# main.net
KiCad netlist of a schematic drawn in EAGLE
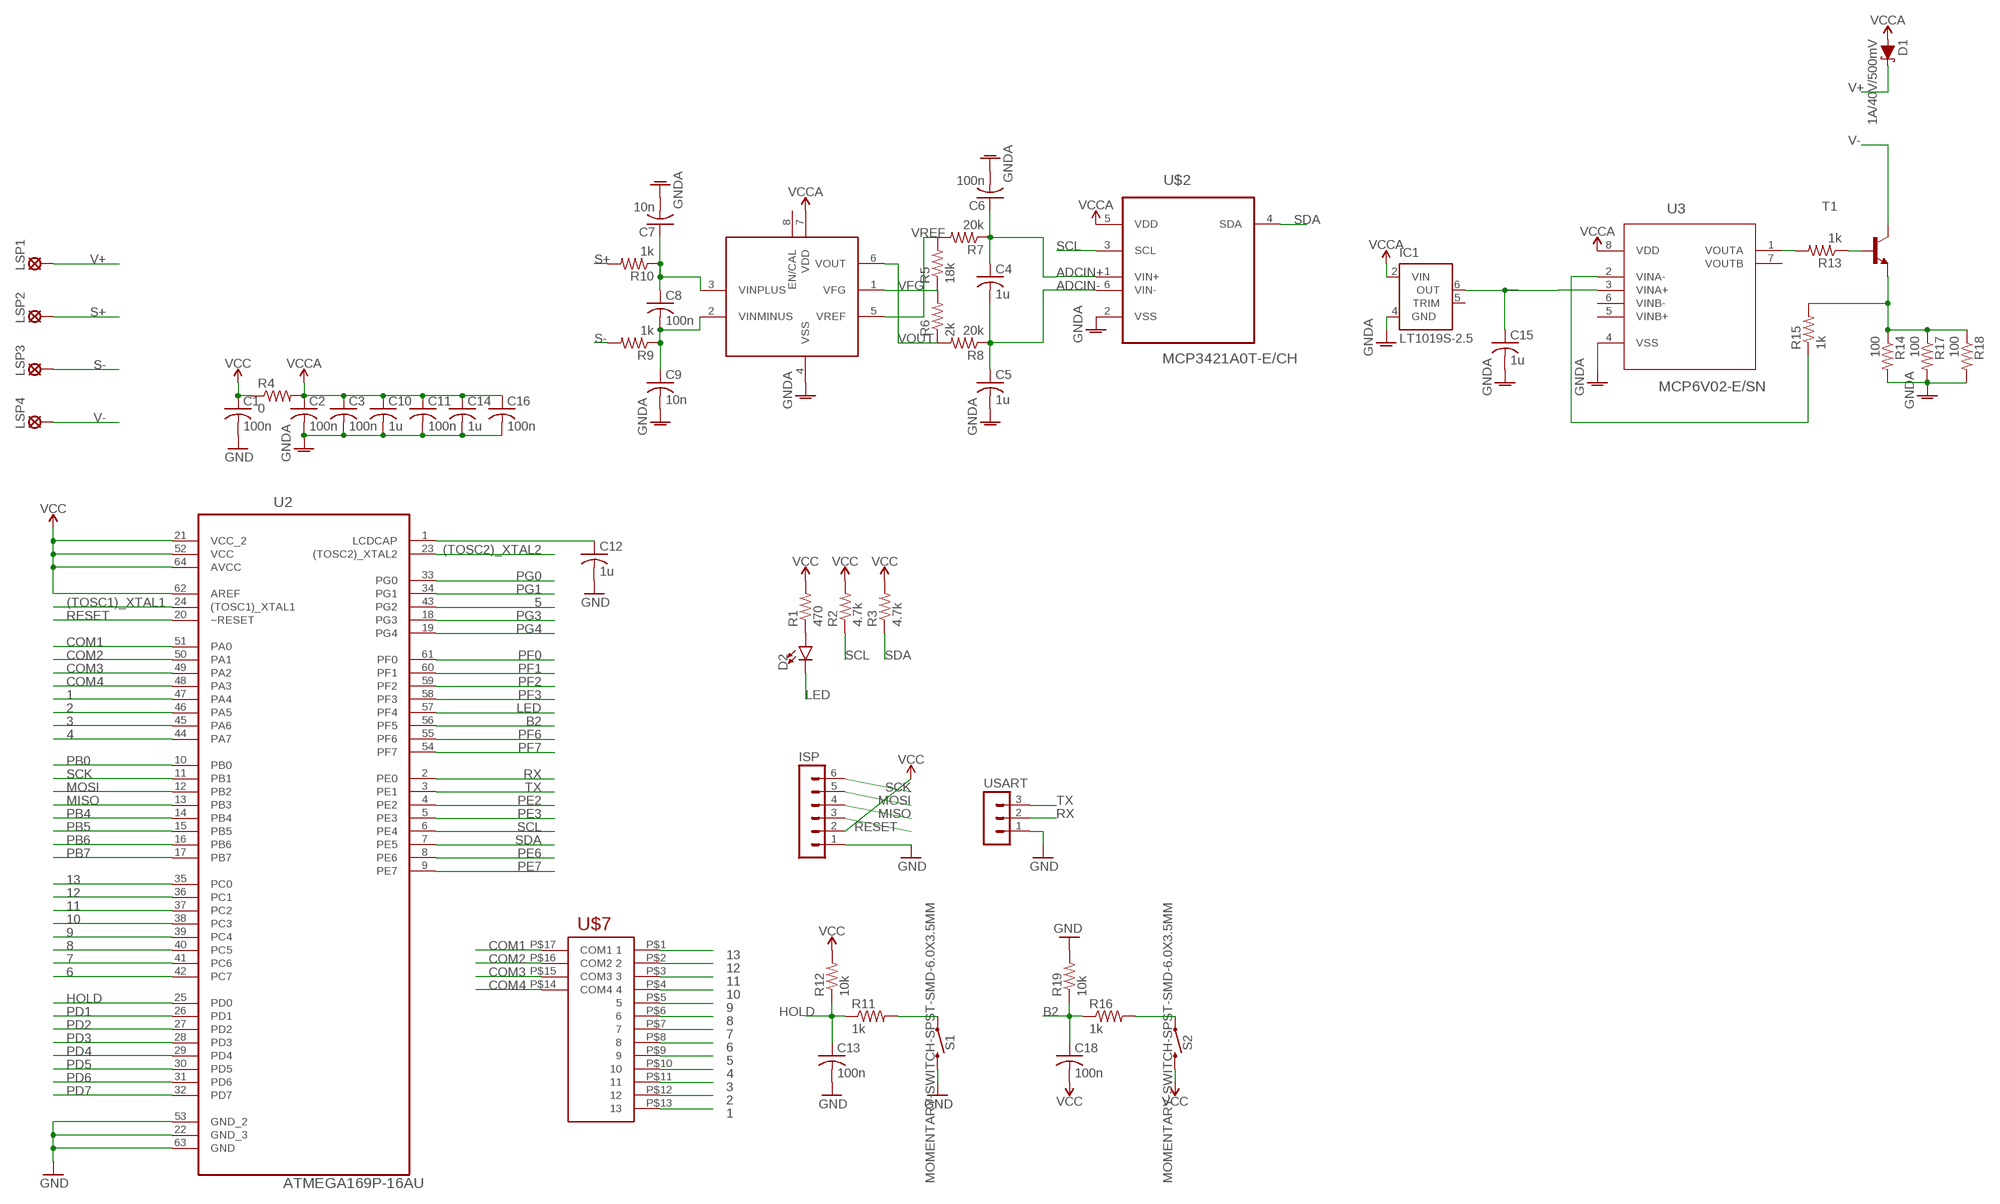
[diagram p0: schematic, sheet 1]

(export (version "E")
  (design (tool "Eeschema 10.0.6"))
  (components
    (comp (ref "C1")
      (value "100n")
      (footprint "eagle-import:C0603")
      (libsource (lib "eagle-import") (part "C-USC0603"))
    )
    (comp (ref "C2")
      (value "100n")
      (footprint "eagle-import:C0603")
      (libsource (lib "eagle-import") (part "C-USC0603"))
    )
    (comp (ref "C3")
      (value "100n")
      (footprint "eagle-import:C0603")
      (libsource (lib "eagle-import") (part "C-USC0603"))
    )
    (comp (ref "C4")
      (value "1u")
      (footprint "eagle-import:C0603")
      (libsource (lib "eagle-import") (part "C-USC0603"))
    )
    (comp (ref "C5")
      (value "1u")
      (footprint "eagle-import:C0603")
      (libsource (lib "eagle-import") (part "C-USC0603"))
    )
    (comp (ref "C6")
      (value "100n")
      (footprint "eagle-import:C0603")
      (libsource (lib "eagle-import") (part "C-USC0603"))
    )
    (comp (ref "C7")
      (value "10n")
      (footprint "eagle-import:C0603")
      (libsource (lib "eagle-import") (part "C-USC0603"))
    )
    (comp (ref "C8")
      (value "100n")
      (footprint "eagle-import:C0603")
      (libsource (lib "eagle-import") (part "C-USC0603"))
    )
    (comp (ref "C9")
      (value "10n")
      (footprint "eagle-import:C0603")
      (libsource (lib "eagle-import") (part "C-USC0603"))
    )
    (comp (ref "C10")
      (value "1u")
      (footprint "eagle-import:C0603")
      (libsource (lib "eagle-import") (part "C-USC0603"))
    )
    (comp (ref "C11")
      (value "100n")
      (footprint "eagle-import:C0603")
      (libsource (lib "eagle-import") (part "C-USC0603"))
    )
    (comp (ref "C12")
      (value "1u")
      (footprint "eagle-import:C0603")
      (libsource (lib "eagle-import") (part "C-USC0603"))
    )
    (comp (ref "C13")
      (value "100n")
      (footprint "eagle-import:C0603")
      (libsource (lib "eagle-import") (part "C-USC0603"))
    )
    (comp (ref "C14")
      (value "1u")
      (footprint "eagle-import:C0603")
      (libsource (lib "eagle-import") (part "C-USC0603"))
    )
    (comp (ref "C15")
      (value "1u")
      (footprint "eagle-import:C0603")
      (libsource (lib "eagle-import") (part "C-USC0603"))
    )
    (comp (ref "C16")
      (value "100n")
      (footprint "eagle-import:C0603")
      (libsource (lib "eagle-import") (part "C-USC0603"))
    )
    (comp (ref "C18")
      (value "100n")
      (footprint "eagle-import:C0603")
      (libsource (lib "eagle-import") (part "C-USC0603"))
    )
    (comp (ref "D1")
      (value "1A/40V/500mV")
      (footprint "eagle-import:SMA-DIODE")
      (libsource (lib "eagle-import") (part "DIODE-SCHOTTKY-SS14"))
    )
    (comp (ref "D2")
      (value "LED5MM")
      (footprint "eagle-import:LED_5MM")
      (libsource (lib "eagle-import") (part "LED5MM"))
    )
    (comp (ref "IC1")
      (value "LT1019S-2.5")
      (footprint "eagle-import:SOIC8")
      (fields (field (name "MPN") "LT1019CS8-2.5#PBF"))
      (libsource (lib "eagle-import") (part "LT1019?S-2.5"))
    )
    (comp (ref "ISP")
      (value "MA06-1")
      (footprint "eagle-import:MA06-1")
      (libsource (lib "eagle-import") (part "MA06-1"))
    )
    (comp (ref "LSP1")
      (value "MCS08")
      (footprint "eagle-import:MCS08")
      (libsource (lib "eagle-import") (part "MCS08"))
    )
    (comp (ref "LSP2")
      (value "MCS08")
      (footprint "eagle-import:MCS08")
      (libsource (lib "eagle-import") (part "MCS08"))
    )
    (comp (ref "LSP3")
      (value "MCS08")
      (footprint "eagle-import:MCS08")
      (libsource (lib "eagle-import") (part "MCS08"))
    )
    (comp (ref "LSP4")
      (value "MCS08")
      (footprint "eagle-import:MCS08")
      (libsource (lib "eagle-import") (part "MCS08"))
    )
    (comp (ref "R1")
      (value "470")
      (footprint "eagle-import:R0603")
      (libsource (lib "eagle-import") (part "R-US_R0603"))
    )
    (comp (ref "R2")
      (value "4.7k")
      (footprint "eagle-import:R0603")
      (libsource (lib "eagle-import") (part "R-US_R0603"))
    )
    (comp (ref "R3")
      (value "4.7k")
      (footprint "eagle-import:R0603")
      (libsource (lib "eagle-import") (part "R-US_R0603"))
    )
    (comp (ref "R4")
      (value "0")
      (footprint "eagle-import:0309_12")
      (libsource (lib "eagle-import") (part "R-US_0309/12"))
    )
    (comp (ref "R5")
      (value "18k")
      (footprint "eagle-import:R0603")
      (libsource (lib "eagle-import") (part "R-US_R0603"))
    )
    (comp (ref "R6")
      (value "2k")
      (footprint "eagle-import:R0603")
      (libsource (lib "eagle-import") (part "R-US_R0603"))
    )
    (comp (ref "R7")
      (value "20k")
      (footprint "eagle-import:R0603")
      (libsource (lib "eagle-import") (part "R-US_R0603"))
    )
    (comp (ref "R8")
      (value "20k")
      (footprint "eagle-import:R0603")
      (libsource (lib "eagle-import") (part "R-US_R0603"))
    )
    (comp (ref "R9")
      (value "1k")
      (footprint "eagle-import:R0603")
      (libsource (lib "eagle-import") (part "R-US_R0603"))
    )
    (comp (ref "R10")
      (value "1k")
      (footprint "eagle-import:R0603")
      (libsource (lib "eagle-import") (part "R-US_R0603"))
    )
    (comp (ref "R11")
      (value "1k")
      (footprint "eagle-import:R0603")
      (libsource (lib "eagle-import") (part "R-US_R0603"))
    )
    (comp (ref "R12")
      (value "10k")
      (footprint "eagle-import:R0603")
      (libsource (lib "eagle-import") (part "R-US_R0603"))
    )
    (comp (ref "R13")
      (value "1k")
      (footprint "eagle-import:R0603")
      (libsource (lib "eagle-import") (part "R-US_R0603"))
    )
    (comp (ref "R14")
      (value "100")
      (footprint "eagle-import:R0603")
      (libsource (lib "eagle-import") (part "R-US_R0603"))
    )
    (comp (ref "R15")
      (value "1k")
      (footprint "eagle-import:R0603")
      (libsource (lib "eagle-import") (part "R-US_R0603"))
    )
    (comp (ref "R16")
      (value "1k")
      (footprint "eagle-import:R0603")
      (libsource (lib "eagle-import") (part "R-US_R0603"))
    )
    (comp (ref "R17")
      (value "100")
      (footprint "eagle-import:R0603")
      (libsource (lib "eagle-import") (part "R-US_R0603"))
    )
    (comp (ref "R18")
      (value "100")
      (footprint "eagle-import:R0603")
      (libsource (lib "eagle-import") (part "R-US_R0603"))
    )
    (comp (ref "R19")
      (value "10k")
      (footprint "eagle-import:R0603")
      (libsource (lib "eagle-import") (part "R-US_R0603"))
    )
    (comp (ref "S1")
      (value "MOMENTARY-SWITCH-SPST-SMD-6.0X3.5MM")
      (footprint "eagle-import:TACTILE_SWITCH_SMD_6.0X3.5MM")
      (libsource (lib "eagle-import") (part "MOMENTARY-SWITCH-SPST-SMD-6.0X3.5MM"))
    )
    (comp (ref "S2")
      (value "MOMENTARY-SWITCH-SPST-SMD-6.0X3.5MM")
      (footprint "eagle-import:TACTILE_SWITCH_SMD_6.0X3.5MM")
      (libsource (lib "eagle-import") (part "MOMENTARY-SWITCH-SPST-SMD-6.0X3.5MM"))
    )
    (comp (ref "T1")
      (value "MMBT3904LT1-NPN-SOT23-BEC")
      (footprint "eagle-import:SOT23-BEC")
      (libsource (lib "eagle-import") (part "-NPN-SOT23-BECMMBT3904LT1"))
    )
    (comp (ref "U$2")
      (value "MCP3421A0T-E/CH")
      (footprint "eagle-import:SOT95P270X145-6N")
      (libsource (lib "eagle-import") (part "MCP3421A0T-E/CH"))
    )
    (comp (ref "U$3")
      (value "MCP6N11")
      (footprint "eagle-import:SOIC8")
      (libsource (lib "eagle-import") (part "MCP6N11"))
    )
    (comp (ref "U$7")
      (value "GDC0570_LCD")
      (footprint "eagle-import:GDC0570_LCD")
      (libsource (lib "eagle-import") (part "GDC0570_LCD"))
    )
    (comp (ref "U2")
      (value "ATMEGA169P-16AU")
      (footprint "eagle-import:QFP80P1600X1600X120-64N")
      (libsource (lib "eagle-import") (part "ATMEGA169P-16AU"))
    )
    (comp (ref "U3")
      (value "MCP6V02-E/SN")
      (footprint "eagle-import:SOIC127P600X175-8N")
      (libsource (lib "eagle-import") (part "MCP6V02-E/SN"))
    )
    (comp (ref "USART")
      (value "MA03-1")
      (footprint "eagle-import:MA03-1")
      (libsource (lib "eagle-import") (part "MA03-1"))
    )
  )
  (nets
    (net (code "1") (name "/(TOSC1)_XTAL1") (class "Default")
      (node (ref "U2") (pin "24") (pinfunction "(TOSC1)_XTAL1_24") (pintype "input"))
    )
    (net (code "2") (name "/(TOSC2)_XTAL2") (class "Default")
      (node (ref "U2") (pin "23") (pinfunction "(TOSC2)_XTAL2_23") (pintype "output"))
    )
    (net (code "3") (name "/1") (class "Default")
      (node (ref "U$7") (pin "P$13") (pinfunction "13_P$13") (pintype "bidirectional"))
      (node (ref "U2") (pin "47") (pinfunction "PA4_47") (pintype "bidirectional"))
    )
    (net (code "4") (name "/2") (class "Default")
      (node (ref "U$7") (pin "P$12") (pinfunction "12_P$12") (pintype "bidirectional"))
      (node (ref "U2") (pin "46") (pinfunction "PA5_46") (pintype "bidirectional"))
    )
    (net (code "5") (name "/3") (class "Default")
      (node (ref "U$7") (pin "P$11") (pinfunction "11_P$11") (pintype "bidirectional"))
      (node (ref "U2") (pin "45") (pinfunction "PA6_45") (pintype "bidirectional"))
    )
    (net (code "6") (name "/4") (class "Default")
      (node (ref "U$7") (pin "P$10") (pinfunction "10_P$10") (pintype "bidirectional"))
      (node (ref "U2") (pin "44") (pinfunction "PA7_44") (pintype "bidirectional"))
    )
    (net (code "7") (name "/5") (class "Default")
      (node (ref "U$7") (pin "P$9") (pinfunction "9_P$9") (pintype "bidirectional"))
      (node (ref "U2") (pin "43") (pinfunction "PG2_43") (pintype "bidirectional"))
    )
    (net (code "8") (name "/6") (class "Default")
      (node (ref "U$7") (pin "P$8") (pinfunction "8_P$8") (pintype "bidirectional"))
      (node (ref "U2") (pin "42") (pinfunction "PC7_42") (pintype "bidirectional"))
    )
    (net (code "9") (name "/7") (class "Default")
      (node (ref "U$7") (pin "P$7") (pinfunction "7_P$7") (pintype "bidirectional"))
      (node (ref "U2") (pin "41") (pinfunction "PC6_41") (pintype "bidirectional"))
    )
    (net (code "10") (name "/8") (class "Default")
      (node (ref "U$7") (pin "P$6") (pinfunction "6_P$6") (pintype "bidirectional"))
      (node (ref "U2") (pin "40") (pinfunction "PC5_40") (pintype "bidirectional"))
    )
    (net (code "11") (name "/9") (class "Default")
      (node (ref "U$7") (pin "P$5") (pinfunction "5_P$5") (pintype "bidirectional"))
      (node (ref "U2") (pin "39") (pinfunction "PC4_39") (pintype "bidirectional"))
    )
    (net (code "12") (name "/10") (class "Default")
      (node (ref "U$7") (pin "P$4") (pinfunction "4_P$4") (pintype "bidirectional"))
      (node (ref "U2") (pin "38") (pinfunction "PC3_38") (pintype "bidirectional"))
    )
    (net (code "13") (name "/11") (class "Default")
      (node (ref "U$7") (pin "P$3") (pinfunction "3_P$3") (pintype "bidirectional"))
      (node (ref "U2") (pin "37") (pinfunction "PC2_37") (pintype "bidirectional"))
    )
    (net (code "14") (name "/12") (class "Default")
      (node (ref "U$7") (pin "P$2") (pinfunction "2_P$2") (pintype "bidirectional"))
      (node (ref "U2") (pin "36") (pinfunction "PC1_36") (pintype "bidirectional"))
    )
    (net (code "15") (name "/13") (class "Default")
      (node (ref "U$7") (pin "P$1") (pinfunction "1_P$1") (pintype "bidirectional"))
      (node (ref "U2") (pin "35") (pinfunction "PC0_35") (pintype "bidirectional"))
    )
    (net (code "16") (name "/ADCIN+") (class "Default")
      (node (ref "C4") (pin "1") (pinfunction "1_1") (pintype "passive"))
      (node (ref "C6") (pin "1") (pinfunction "1_1") (pintype "passive"))
      (node (ref "R7") (pin "1") (pinfunction "1_1") (pintype "passive"))
      (node (ref "U$2") (pin "1") (pinfunction "VIN+_1") (pintype "input"))
    )
    (net (code "17") (name "/ADCIN-") (class "Default")
      (node (ref "C4") (pin "2") (pinfunction "2_2") (pintype "passive"))
      (node (ref "C5") (pin "1") (pinfunction "1_1") (pintype "passive"))
      (node (ref "R8") (pin "1") (pinfunction "1_1") (pintype "passive"))
      (node (ref "U$2") (pin "6") (pinfunction "VIN-_6") (pintype "input"))
    )
    (net (code "18") (name "/B2") (class "Default")
      (node (ref "C18") (pin "1") (pinfunction "1_1") (pintype "passive"))
      (node (ref "R16") (pin "1") (pinfunction "1_1") (pintype "passive"))
      (node (ref "R19") (pin "1") (pinfunction "1_1") (pintype "passive"))
      (node (ref "U2") (pin "56") (pinfunction "PF5_56") (pintype "bidirectional"))
    )
    (net (code "19") (name "/COM1") (class "Default")
      (node (ref "U$7") (pin "P$17") (pinfunction "COM1_P$17") (pintype "bidirectional"))
      (node (ref "U2") (pin "51") (pinfunction "PA0_51") (pintype "bidirectional"))
    )
    (net (code "20") (name "/COM2") (class "Default")
      (node (ref "U$7") (pin "P$16") (pinfunction "COM2_P$16") (pintype "bidirectional"))
      (node (ref "U2") (pin "50") (pinfunction "PA1_50") (pintype "bidirectional"))
    )
    (net (code "21") (name "/COM3") (class "Default")
      (node (ref "U$7") (pin "P$15") (pinfunction "COM3_P$15") (pintype "bidirectional"))
      (node (ref "U2") (pin "49") (pinfunction "PA2_49") (pintype "bidirectional"))
    )
    (net (code "22") (name "/COM4") (class "Default")
      (node (ref "U$7") (pin "P$14") (pinfunction "COM4_P$14") (pintype "bidirectional"))
      (node (ref "U2") (pin "48") (pinfunction "PA3_48") (pintype "bidirectional"))
    )
    (net (code "23") (name "/HOLD") (class "Default")
      (node (ref "C13") (pin "1") (pinfunction "1_1") (pintype "passive"))
      (node (ref "R11") (pin "1") (pinfunction "1_1") (pintype "passive"))
      (node (ref "R12") (pin "1") (pinfunction "1_1") (pintype "passive"))
      (node (ref "U2") (pin "25") (pinfunction "PD0_25") (pintype "bidirectional"))
    )
    (net (code "24") (name "/LED") (class "Default")
      (node (ref "D2") (pin "K") (pinfunction "C_K") (pintype "passive"))
      (node (ref "U2") (pin "57") (pinfunction "PF4_57") (pintype "bidirectional"))
    )
    (net (code "25") (name "/MISO") (class "Default")
      (node (ref "ISP") (pin "4") (pinfunction "4_4") (pintype "passive"))
      (node (ref "U2") (pin "13") (pinfunction "PB3_13") (pintype "bidirectional"))
    )
    (net (code "26") (name "/MOSI") (class "Default")
      (node (ref "ISP") (pin "5") (pinfunction "5_5") (pintype "passive"))
      (node (ref "U2") (pin "12") (pinfunction "PB2_12") (pintype "bidirectional"))
    )
    (net (code "27") (name "/PB0") (class "Default")
      (node (ref "U2") (pin "10") (pinfunction "PB0_10") (pintype "bidirectional"))
    )
    (net (code "28") (name "/PB4") (class "Default")
      (node (ref "U2") (pin "14") (pinfunction "PB4_14") (pintype "bidirectional"))
    )
    (net (code "29") (name "/PB5") (class "Default")
      (node (ref "U2") (pin "15") (pinfunction "PB5_15") (pintype "bidirectional"))
    )
    (net (code "30") (name "/PB6") (class "Default")
      (node (ref "U2") (pin "16") (pinfunction "PB6_16") (pintype "bidirectional"))
    )
    (net (code "31") (name "/PB7") (class "Default")
      (node (ref "U2") (pin "17") (pinfunction "PB7_17") (pintype "bidirectional"))
    )
    (net (code "32") (name "/PD1") (class "Default")
      (node (ref "U2") (pin "26") (pinfunction "PD1_26") (pintype "bidirectional"))
    )
    (net (code "33") (name "/PD2") (class "Default")
      (node (ref "U2") (pin "27") (pinfunction "PD2_27") (pintype "bidirectional"))
    )
    (net (code "34") (name "/PD3") (class "Default")
      (node (ref "U2") (pin "28") (pinfunction "PD3_28") (pintype "bidirectional"))
    )
    (net (code "35") (name "/PD4") (class "Default")
      (node (ref "U2") (pin "29") (pinfunction "PD4_29") (pintype "bidirectional"))
    )
    (net (code "36") (name "/PD5") (class "Default")
      (node (ref "U2") (pin "30") (pinfunction "PD5_30") (pintype "bidirectional"))
    )
    (net (code "37") (name "/PD6") (class "Default")
      (node (ref "U2") (pin "31") (pinfunction "PD6_31") (pintype "bidirectional"))
    )
    (net (code "38") (name "/PD7") (class "Default")
      (node (ref "U2") (pin "32") (pinfunction "PD7_32") (pintype "bidirectional"))
    )
    (net (code "39") (name "/PE2") (class "Default")
      (node (ref "U2") (pin "4") (pinfunction "PE2_4") (pintype "bidirectional"))
    )
    (net (code "40") (name "/PE3") (class "Default")
      (node (ref "U2") (pin "5") (pinfunction "PE3_5") (pintype "bidirectional"))
    )
    (net (code "41") (name "/PE6") (class "Default")
      (node (ref "U2") (pin "8") (pinfunction "PE6_8") (pintype "bidirectional"))
    )
    (net (code "42") (name "/PE7") (class "Default")
      (node (ref "U2") (pin "9") (pinfunction "PE7_9") (pintype "bidirectional"))
    )
    (net (code "43") (name "/PF0") (class "Default")
      (node (ref "U2") (pin "61") (pinfunction "PF0_61") (pintype "bidirectional"))
    )
    (net (code "44") (name "/PF1") (class "Default")
      (node (ref "U2") (pin "60") (pinfunction "PF1_60") (pintype "bidirectional"))
    )
    (net (code "45") (name "/PF2") (class "Default")
      (node (ref "U2") (pin "59") (pinfunction "PF2_59") (pintype "bidirectional"))
    )
    (net (code "46") (name "/PF3") (class "Default")
      (node (ref "U2") (pin "58") (pinfunction "PF3_58") (pintype "bidirectional"))
    )
    (net (code "47") (name "/PF6") (class "Default")
      (node (ref "U2") (pin "55") (pinfunction "PF6_55") (pintype "bidirectional"))
    )
    (net (code "48") (name "/PF7") (class "Default")
      (node (ref "U2") (pin "54") (pinfunction "PF7_54") (pintype "bidirectional"))
    )
    (net (code "49") (name "/PG0") (class "Default")
      (node (ref "U2") (pin "33") (pinfunction "PG0_33") (pintype "bidirectional"))
    )
    (net (code "50") (name "/PG1") (class "Default")
      (node (ref "U2") (pin "34") (pinfunction "PG1_34") (pintype "bidirectional"))
    )
    (net (code "51") (name "/PG3") (class "Default")
      (node (ref "U2") (pin "18") (pinfunction "PG3_18") (pintype "bidirectional"))
    )
    (net (code "52") (name "/PG4") (class "Default")
      (node (ref "U2") (pin "19") (pinfunction "PG4_19") (pintype "bidirectional"))
    )
    (net (code "53") (name "/RESET") (class "Default")
      (node (ref "ISP") (pin "3") (pinfunction "3_3") (pintype "passive"))
      (node (ref "U2") (pin "20") (pinfunction "~{RESET}_20") (pintype "input"))
    )
    (net (code "54") (name "/RX") (class "Default")
      (node (ref "U2") (pin "2") (pinfunction "PE0_2") (pintype "bidirectional"))
      (node (ref "USART") (pin "2") (pinfunction "2_2") (pintype "passive"))
    )
    (net (code "55") (name "/S+") (class "Default")
      (node (ref "LSP2") (pin "MP") (pinfunction "MP_MP") (pintype "passive"))
      (node (ref "R10") (pin "2") (pinfunction "2_2") (pintype "passive"))
    )
    (net (code "56") (name "/S-") (class "Default")
      (node (ref "LSP3") (pin "MP") (pinfunction "MP_MP") (pintype "passive"))
      (node (ref "R9") (pin "2") (pinfunction "2_2") (pintype "passive"))
    )
    (net (code "57") (name "/SCK") (class "Default")
      (node (ref "ISP") (pin "6") (pinfunction "6_6") (pintype "passive"))
      (node (ref "U2") (pin "11") (pinfunction "PB1_11") (pintype "bidirectional"))
    )
    (net (code "58") (name "/SCL") (class "Default")
      (node (ref "R2") (pin "1") (pinfunction "1_1") (pintype "passive"))
      (node (ref "U$2") (pin "3") (pinfunction "SCL_3") (pintype "input"))
      (node (ref "U2") (pin "6") (pinfunction "PE4_6") (pintype "bidirectional"))
    )
    (net (code "59") (name "/SDA") (class "Default")
      (node (ref "R3") (pin "1") (pinfunction "1_1") (pintype "passive"))
      (node (ref "U$2") (pin "4") (pinfunction "SDA_4") (pintype "bidirectional"))
      (node (ref "U2") (pin "7") (pinfunction "PE5_7") (pintype "bidirectional"))
    )
    (net (code "60") (name "/TX") (class "Default")
      (node (ref "U2") (pin "3") (pinfunction "PE1_3") (pintype "bidirectional"))
      (node (ref "USART") (pin "3") (pinfunction "3_3") (pintype "passive"))
    )
    (net (code "61") (name "/V+") (class "Default")
      (node (ref "D1") (pin "C") (pinfunction "C_C") (pintype "passive"))
      (node (ref "LSP1") (pin "MP") (pinfunction "MP_MP") (pintype "passive"))
    )
    (net (code "62") (name "/V-") (class "Default")
      (node (ref "LSP4") (pin "MP") (pinfunction "MP_MP") (pintype "passive"))
      (node (ref "T1") (pin "C") (pinfunction "C_C") (pintype "passive"))
    )
    (net (code "63") (name "/VFG") (class "Default")
      (node (ref "R5") (pin "1") (pinfunction "1_1") (pintype "passive"))
      (node (ref "R6") (pin "2") (pinfunction "2_2") (pintype "passive"))
      (node (ref "U$3") (pin "1") (pinfunction "VFG_1") (pintype "bidirectional"))
    )
    (net (code "64") (name "/VOUT") (class "Default")
      (node (ref "R6") (pin "1") (pinfunction "1_1") (pintype "passive"))
      (node (ref "R8") (pin "2") (pinfunction "2_2") (pintype "passive"))
      (node (ref "U$3") (pin "6") (pinfunction "VOUT_6") (pintype "bidirectional"))
    )
    (net (code "65") (name "/VREF") (class "Default")
      (node (ref "R5") (pin "2") (pinfunction "2_2") (pintype "passive"))
      (node (ref "R7") (pin "2") (pinfunction "2_2") (pintype "passive"))
      (node (ref "U$3") (pin "5") (pinfunction "VREF_5") (pintype "bidirectional"))
    )
    (net (code "66") (name "GND") (class "Default")
      (node (ref "C1") (pin "2") (pinfunction "2_2") (pintype "passive"))
      (node (ref "C12") (pin "2") (pinfunction "2_2") (pintype "passive"))
      (node (ref "C13") (pin "2") (pinfunction "2_2") (pintype "passive"))
      (node (ref "ISP") (pin "1") (pinfunction "1_1") (pintype "passive"))
      (node (ref "R19") (pin "2") (pinfunction "2_2") (pintype "passive"))
      (node (ref "S1") (pin "2") (pinfunction "2_2") (pintype "passive"))
      (node (ref "U2") (pin "22") (pinfunction "GND_3_22") (pintype "passive"))
      (node (ref "U2") (pin "53") (pinfunction "GND_2_53") (pintype "passive"))
      (node (ref "U2") (pin "63") (pinfunction "GND_63") (pintype "passive"))
      (node (ref "USART") (pin "1") (pinfunction "1_1") (pintype "passive"))
    )
    (net (code "67") (name "GNDA") (class "Default")
      (node (ref "C10") (pin "2") (pinfunction "2_2") (pintype "passive"))
      (node (ref "C11") (pin "2") (pinfunction "2_2") (pintype "passive"))
      (node (ref "C14") (pin "2") (pinfunction "2_2") (pintype "passive"))
      (node (ref "C15") (pin "2") (pinfunction "2_2") (pintype "passive"))
      (node (ref "C16") (pin "2") (pinfunction "2_2") (pintype "passive"))
      (node (ref "C2") (pin "2") (pinfunction "2_2") (pintype "passive"))
      (node (ref "C3") (pin "2") (pinfunction "2_2") (pintype "passive"))
      (node (ref "C5") (pin "2") (pinfunction "2_2") (pintype "passive"))
      (node (ref "C6") (pin "2") (pinfunction "2_2") (pintype "passive"))
      (node (ref "C7") (pin "2") (pinfunction "2_2") (pintype "passive"))
      (node (ref "C9") (pin "2") (pinfunction "2_2") (pintype "passive"))
      (node (ref "IC1") (pin "4") (pinfunction "GND_4") (pintype "power_in"))
      (node (ref "R14") (pin "2") (pinfunction "2_2") (pintype "passive"))
      (node (ref "R17") (pin "2") (pinfunction "2_2") (pintype "passive"))
      (node (ref "R18") (pin "2") (pinfunction "2_2") (pintype "passive"))
      (node (ref "U$2") (pin "2") (pinfunction "VSS_2") (pintype "passive"))
      (node (ref "U$3") (pin "4") (pinfunction "VSS_4") (pintype "bidirectional"))
      (node (ref "U3") (pin "4") (pinfunction "VSS_4") (pintype "power_in"))
    )
    (net (code "68") (name "Net-(D2-PadA)") (class "Default")
      (node (ref "D2") (pin "A") (pinfunction "A_A") (pintype "passive"))
      (node (ref "R1") (pin "1") (pinfunction "1_1") (pintype "passive"))
    )
    (net (code "69") (name "Net-(IC1-OUT)") (class "Default")
      (node (ref "C15") (pin "1") (pinfunction "1_1") (pintype "passive"))
      (node (ref "IC1") (pin "6") (pinfunction "OUT_6") (pintype "input"))
      (node (ref "U3") (pin "3") (pinfunction "VINA+_3") (pintype "input"))
    )
    (net (code "70") (name "Net-(R11-Pad2)") (class "Default")
      (node (ref "R11") (pin "2") (pinfunction "2_2") (pintype "passive"))
      (node (ref "S1") (pin "1") (pinfunction "1_1") (pintype "passive"))
    )
    (net (code "71") (name "Net-(R13-Pad1)") (class "Default")
      (node (ref "R13") (pin "1") (pinfunction "1_1") (pintype "passive"))
      (node (ref "T1") (pin "B") (pinfunction "B_B") (pintype "passive"))
    )
    (net (code "72") (name "Net-(R14-Pad1)") (class "Default")
      (node (ref "R14") (pin "1") (pinfunction "1_1") (pintype "passive"))
      (node (ref "R15") (pin "2") (pinfunction "2_2") (pintype "passive"))
      (node (ref "R17") (pin "1") (pinfunction "1_1") (pintype "passive"))
      (node (ref "R18") (pin "1") (pinfunction "1_1") (pintype "passive"))
      (node (ref "T1") (pin "E") (pinfunction "E_E") (pintype "passive"))
    )
    (net (code "73") (name "Net-(R16-Pad2)") (class "Default")
      (node (ref "R16") (pin "2") (pinfunction "2_2") (pintype "passive"))
      (node (ref "S2") (pin "1") (pinfunction "1_1") (pintype "passive"))
    )
    (net (code "74") (name "Net-(U$3-VINMINUS)") (class "Default")
      (node (ref "C8") (pin "2") (pinfunction "2_2") (pintype "passive"))
      (node (ref "C9") (pin "1") (pinfunction "1_1") (pintype "passive"))
      (node (ref "R9") (pin "1") (pinfunction "1_1") (pintype "passive"))
      (node (ref "U$3") (pin "2") (pinfunction "VINMINUS_2") (pintype "bidirectional"))
    )
    (net (code "75") (name "Net-(U$3-VINPLUS)") (class "Default")
      (node (ref "C7") (pin "1") (pinfunction "1_1") (pintype "passive"))
      (node (ref "C8") (pin "1") (pinfunction "1_1") (pintype "passive"))
      (node (ref "R10") (pin "1") (pinfunction "1_1") (pintype "passive"))
      (node (ref "U$3") (pin "3") (pinfunction "VINPLUS_3") (pintype "bidirectional"))
    )
    (net (code "76") (name "Net-(U2-LCDCAP)") (class "Default")
      (node (ref "C12") (pin "1") (pinfunction "1_1") (pintype "passive"))
      (node (ref "U2") (pin "1") (pinfunction "LCDCAP_1") (pintype "passive"))
    )
    (net (code "77") (name "Net-(U3-VINA-)") (class "Default")
      (node (ref "R15") (pin "1") (pinfunction "1_1") (pintype "passive"))
      (node (ref "U3") (pin "2") (pinfunction "VINA-_2") (pintype "input"))
    )
    (net (code "78") (name "Net-(U3-VOUTA)") (class "Default")
      (node (ref "R13") (pin "2") (pinfunction "2_2") (pintype "passive"))
      (node (ref "U3") (pin "1") (pinfunction "VOUTA_1") (pintype "output"))
    )
    (net (code "79") (name "VCC") (class "Default")
      (node (ref "C1") (pin "1") (pinfunction "1_1") (pintype "passive"))
      (node (ref "C18") (pin "2") (pinfunction "2_2") (pintype "passive"))
      (node (ref "ISP") (pin "2") (pinfunction "2_2") (pintype "passive"))
      (node (ref "R1") (pin "2") (pinfunction "2_2") (pintype "passive"))
      (node (ref "R12") (pin "2") (pinfunction "2_2") (pintype "passive"))
      (node (ref "R2") (pin "2") (pinfunction "2_2") (pintype "passive"))
      (node (ref "R3") (pin "2") (pinfunction "2_2") (pintype "passive"))
      (node (ref "R4") (pin "1") (pinfunction "1_1") (pintype "passive"))
      (node (ref "S2") (pin "2") (pinfunction "2_2") (pintype "passive"))
      (node (ref "U2") (pin "21") (pinfunction "VCC_2_21") (pintype "power_in"))
      (node (ref "U2") (pin "52") (pinfunction "VCC_52") (pintype "power_in"))
      (node (ref "U2") (pin "62") (pinfunction "AREF_62") (pintype "input"))
      (node (ref "U2") (pin "64") (pinfunction "AVCC_64") (pintype "power_in"))
    )
    (net (code "80") (name "VCCA") (class "Default")
      (node (ref "C10") (pin "1") (pinfunction "1_1") (pintype "passive"))
      (node (ref "C11") (pin "1") (pinfunction "1_1") (pintype "passive"))
      (node (ref "C14") (pin "1") (pinfunction "1_1") (pintype "passive"))
      (node (ref "C16") (pin "1") (pinfunction "1_1") (pintype "passive"))
      (node (ref "C2") (pin "1") (pinfunction "1_1") (pintype "passive"))
      (node (ref "C3") (pin "1") (pinfunction "1_1") (pintype "passive"))
      (node (ref "D1") (pin "A") (pinfunction "A_A") (pintype "passive"))
      (node (ref "IC1") (pin "2") (pinfunction "VIN_2") (pintype "input"))
      (node (ref "R4") (pin "2") (pinfunction "2_2") (pintype "passive"))
      (node (ref "U$2") (pin "5") (pinfunction "VDD_5") (pintype "power_in"))
      (node (ref "U$3") (pin "7") (pinfunction "VDD_7") (pintype "bidirectional"))
      (node (ref "U3") (pin "8") (pinfunction "VDD_8") (pintype "power_in"))
    )
    (net (code "81") (name "unconnected-(IC1-TRIM-Pad5)") (class "Default")
      (node (ref "IC1") (pin "5") (pinfunction "TRIM_5") (pintype "passive"))
    )
    (net (code "82") (name "unconnected-(U$3-EN{slash}CAL-Pad8)") (class "Default")
      (node (ref "U$3") (pin "8") (pinfunction "EN/CAL_8") (pintype "bidirectional"))
    )
    (net (code "83") (name "unconnected-(U3-VINB+-Pad5)") (class "Default")
      (node (ref "U3") (pin "5") (pinfunction "VINB+_5") (pintype "input"))
    )
    (net (code "84") (name "unconnected-(U3-VINB--Pad6)") (class "Default")
      (node (ref "U3") (pin "6") (pinfunction "VINB-_6") (pintype "input"))
    )
    (net (code "85") (name "unconnected-(U3-VOUTB-Pad7)") (class "Default")
      (node (ref "U3") (pin "7") (pinfunction "VOUTB_7") (pintype "output"))
    )
  )
)
